# 18650_1S1P_PTH.net
KiCad netlist of a schematic drawn in EAGLE
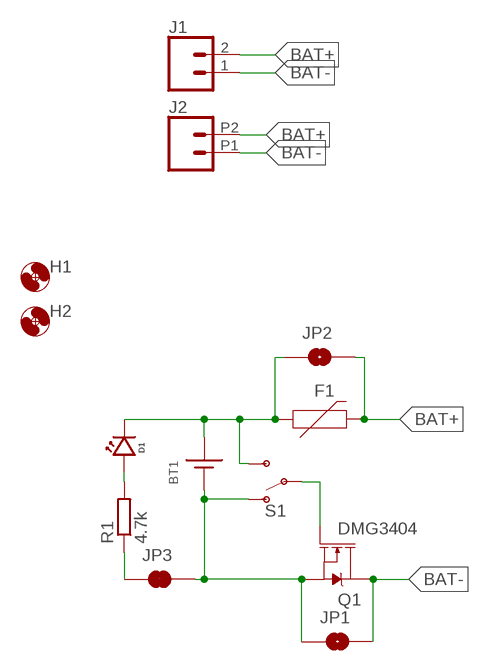
[diagram p0: schematic, sheet 1]

(export (version "E")
  (design (tool "Eeschema 10.0.6"))
  (components
    (comp (ref "BT1")
      (value "18650NO_PROTEC")
      (footprint "eagle-import:BATT_18650_CLIP")
      (fields (field (name "MF") "Keystone") (field (name "MPN") "54"))
      (libsource (lib "eagle-import") (part "18650NO_PROTEC"))
    )
    (comp (ref "D1")
      (value "LED0603")
      (footprint "eagle-import:LED_0603")
      (libsource (lib "eagle-import") (part "LED0603"))
    )
    (comp (ref "F1")
      (value "PPTC1.75A1210")
      (footprint "eagle-import:1210_BOURNS")
      (fields (field (name "MF") "Bourns") (field (name "MPN") "MF-USMF175X-2"))
      (libsource (lib "eagle-import") (part "PPTC12101.75A"))
    )
    (comp (ref "H1")
      (value "MOUNTING_HOLE4_NP")
      (footprint "eagle-import:4_40")
      (fields (field (name "MPN") "DNP"))
      (libsource (lib "eagle-import") (part "MOUNTING_HOLE4_NP"))
    )
    (comp (ref "H2")
      (value "MOUNTING_HOLE4_NP")
      (footprint "eagle-import:4_40")
      (fields (field (name "MPN") "DNP"))
      (libsource (lib "eagle-import") (part "MOUNTING_HOLE4_NP"))
    )
    (comp (ref "J1")
      (value "CONN_023.5MM_ROUND_RESTRICT")
      (footprint "eagle-import:SCREWTERMINAL-3.5MM-2_ROUND_RESTRICT")
      (fields (field (name "MF") "On Shore") (field (name "MPN") "OSTTE020161"))
      (libsource (lib "eagle-import") (part "CONN_023.5MM_ROUND_RESTRICT"))
    )
    (comp (ref "J2")
      (value "CONN_022.54_SCREW_ROUND")
      (footprint "eagle-import:1X02_2.54_SCREWTERM_ROUND")
      (fields (field (name "MF") "OnShore") (field (name "MPN") "OSTVN02A150"))
      (libsource (lib "eagle-import") (part "CONN_022.54_SCREW_ROUND"))
    )
    (comp (ref "JP1")
      (value "JUMPER-SMT_2_NO_SILK")
      (footprint "eagle-import:SMT-JUMPER_2_NO_SILK")
      (libsource (lib "eagle-import") (part "JUMPER-SMT_2_NO_SILK"))
    )
    (comp (ref "JP2")
      (value "JUMPER-SMT_2_NO_SILK")
      (footprint "eagle-import:SMT-JUMPER_2_NO_SILK")
      (libsource (lib "eagle-import") (part "JUMPER-SMT_2_NO_SILK"))
    )
    (comp (ref "JP3")
      (value "JUMPER-SMT_2_NC_TRACE_SILK")
      (footprint "eagle-import:SMT-JUMPER_2_NC_TRACE_SILK")
      (libsource (lib "eagle-import") (part "JUMPER-SMT_2_NC_TRACE_SILK"))
    )
    (comp (ref "Q1")
      (value "DMG3404")
      (footprint "eagle-import:SOT23-3")
      (fields (field (name "MF") "Diodes Incorporated") (field (name "MPN") "DMG3404L-7"))
      (libsource (lib "eagle-import") (part "MOSFET-NCH-DMG3404L"))
    )
    (comp (ref "R1")
      (value "4.7k")
      (footprint "eagle-import:R0603")
      (fields (field (name "MF") "Yageo") (field (name "MPN") "RC0603FR-074K7L"))
      (libsource (lib "eagle-import") (part "R-EU_R06034.7K"))
    )
    (comp (ref "S1")
      (value "SPDTOS1020")
      (footprint "eagle-import:OS102011MS2QN1")
      (libsource (lib "eagle-import") (part "SPDTOS1020"))
    )
  )
  (nets
    (net (code "1") (name "BAT+") (class "Default")
      (node (ref "F1") (pin "2") (pinfunction "2_2") (pintype "bidirectional"))
      (node (ref "J1") (pin "2") (pinfunction "2_2") (pintype "passive"))
      (node (ref "J2") (pin "P2") (pinfunction "2_P2") (pintype "passive"))
      (node (ref "JP2") (pin "2") (pinfunction "2_2") (pintype "passive"))
    )
    (net (code "2") (name "BAT-") (class "Default")
      (node (ref "J1") (pin "1") (pinfunction "1_1") (pintype "passive"))
      (node (ref "J2") (pin "P1") (pinfunction "1_P1") (pintype "passive"))
      (node (ref "JP1") (pin "2") (pinfunction "2_2") (pintype "passive"))
      (node (ref "Q1") (pin "3") (pinfunction "D_3") (pintype "bidirectional"))
    )
    (net (code "3") (name "Net-(D1-PadANODE)") (class "Default")
      (node (ref "D1") (pin "ANODE") (pinfunction "ANODE_ANODE") (pintype "power_in"))
      (node (ref "R1") (pin "2") (pinfunction "2_2") (pintype "passive"))
    )
    (net (code "4") (name "Net-(JP3-Pad1)") (class "Default")
      (node (ref "JP3") (pin "1") (pinfunction "1_1") (pintype "passive"))
      (node (ref "R1") (pin "1") (pinfunction "1_1") (pintype "passive"))
    )
    (net (code "5") (name "Net-(Q1-G)") (class "Default")
      (node (ref "Q1") (pin "1") (pinfunction "G_1") (pintype "bidirectional"))
      (node (ref "S1") (pin "2") (pinfunction "P_2") (pintype "passive"))
    )
    (net (code "6") (name "Net-(Q1-S)") (class "Default")
      (node (ref "BT1") (pin "BATT-@1") (pinfunction "-_BATT-@1") (pintype "power_in"))
      (node (ref "BT1") (pin "BATT-@2") (pinfunction "-_BATT-@2") (pintype "power_in"))
      (node (ref "BT1") (pin "BATT-@3") (pinfunction "-_BATT-@3") (pintype "power_in"))
      (node (ref "JP1") (pin "1") (pinfunction "1_1") (pintype "passive"))
      (node (ref "JP3") (pin "2") (pinfunction "2_2") (pintype "passive"))
      (node (ref "Q1") (pin "2") (pinfunction "S_2") (pintype "bidirectional"))
      (node (ref "S1") (pin "1") (pinfunction "O_1") (pintype "passive"))
    )
    (net (code "7") (name "Net-(S1-S)") (class "Default")
      (node (ref "BT1") (pin "BATT+@1") (pinfunction "+_BATT+@1") (pintype "power_in"))
      (node (ref "BT1") (pin "BATT+@2") (pinfunction "+_BATT+@2") (pintype "power_in"))
      (node (ref "BT1") (pin "BATT+@3") (pinfunction "+_BATT+@3") (pintype "power_in"))
      (node (ref "D1") (pin "CATHODE") (pinfunction "CATHODE_CATHODE") (pintype "power_in"))
      (node (ref "F1") (pin "1") (pinfunction "1_1") (pintype "bidirectional"))
      (node (ref "JP2") (pin "1") (pinfunction "1_1") (pintype "passive"))
      (node (ref "S1") (pin "3") (pinfunction "S_3") (pintype "passive"))
    )
  )
)
